# USB.net
KiCad netlist of a schematic drawn in Altium Designer
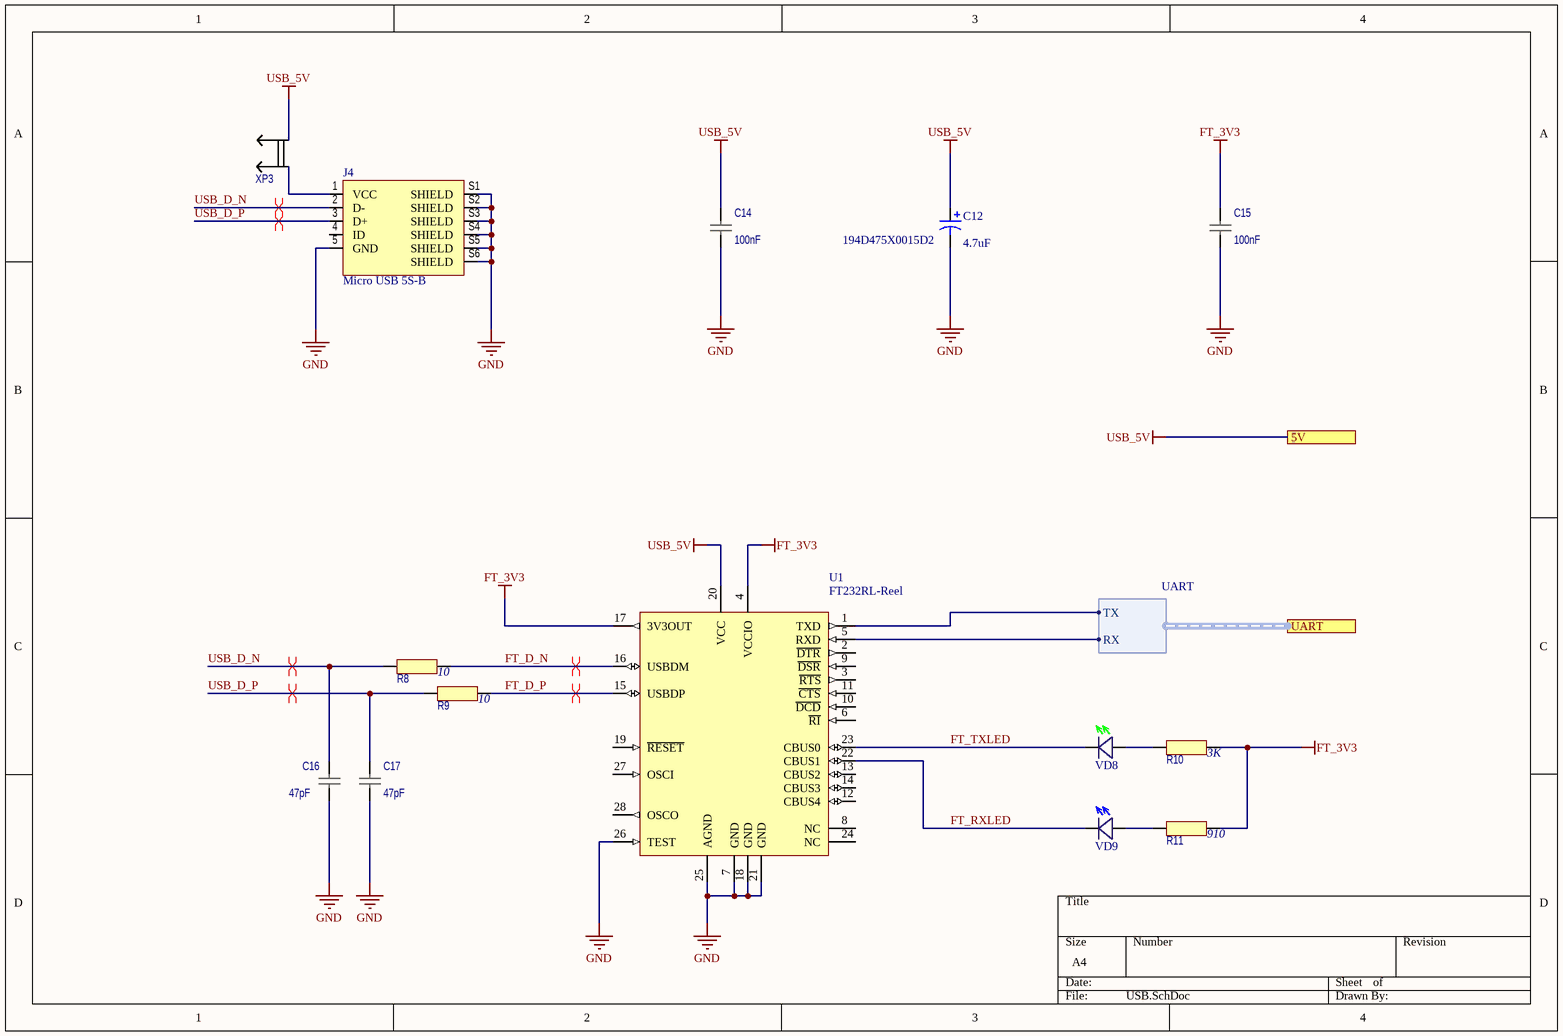
[diagram p0: USB.SchDoc]

(export (version "E")
  (design (tool "Eeschema 10.0.6"))
  (components
    (comp (ref "C12")
      (value "194D475X0015D2")
      (footprint "D")
      (fields (field (name "ALTIUM_VALUE") "4.7uF") (field (name "PUBLISHER") "Altium Limited"))
      (libsource (lib "Vishay Sprague Tantalum Chip Capacitor") (part "194D475X0015D2"))
    )
    (comp (ref "C14")
      (value "100nF")
      (footprint "C0805")
      (fields (field (name "TOLERANCE") "%") (field (name "VOLTAGE") "B") (field (name "Comment") "C0805"))
      (libsource (lib "my_AP_lib_sch") (part "C0805"))
    )
    (comp (ref "C15")
      (value "100nF")
      (footprint "C0805")
      (fields (field (name "TOLERANCE") "%") (field (name "VOLTAGE") "B") (field (name "Comment") "C0805"))
      (libsource (lib "my_AP_lib_sch") (part "C0805"))
    )
    (comp (ref "C16")
      (value "47pF")
      (footprint "C0805")
      (fields (field (name "TOLERANCE") "%") (field (name "VOLTAGE") "B") (field (name "Comment") "C0805"))
      (libsource (lib "my_AP_lib_sch") (part "C0805"))
    )
    (comp (ref "C17")
      (value "47pF")
      (footprint "C0805")
      (fields (field (name "TOLERANCE") "%") (field (name "VOLTAGE") "B") (field (name "Comment") "C0805"))
      (libsource (lib "my_AP_lib_sch") (part "C0805"))
    )
    (comp (ref "J4")
      (value "Micro USB 5S-B")
      (footprint "KLS1-233-0-0-1-T")
      (libsource (lib "my_AP_lib_sch") (part "KLS1-233-0-0-1-T"))
    )
    (comp (ref "R8")
      (value "10")
      (footprint "R0805")
      (fields (field (name "Comment") "R0805"))
      (libsource (lib "my_AP_lib_sch") (part "R0805"))
    )
    (comp (ref "R9")
      (value "10")
      (footprint "R0805")
      (fields (field (name "Comment") "R0805"))
      (libsource (lib "my_AP_lib_sch") (part "R0805"))
    )
    (comp (ref "R10")
      (value "3K")
      (footprint "R0805")
      (fields (field (name "Comment") "R0805"))
      (libsource (lib "my_AP_lib_sch") (part "R0805"))
    )
    (comp (ref "R11")
      (value "910")
      (footprint "R0805")
      (fields (field (name "Comment") "R0805"))
      (libsource (lib "my_AP_lib_sch") (part "R0805"))
    )
    (comp (ref "U1")
      (value "FT232RL-Reel")
      (footprint "SSOP-28_N")
      (description "USB UART Asynchronous Serial Data Transfer Chip, 28-pin SSOP, Tape and Reel")
      (fields (field (name "MANUFACTURER") "FTDI"))
      (libsource (lib "FTDI FT Series") (part "FT232RL-Reel"))
    )
    (comp (ref "VD8")
      (value "TO-1608BC-PG")
      (footprint "TO-1608BC-PG")
      (description "LED SMD 1608 705мКд, 120°, 525нМ (Pure Green)")
      (libsource (lib "my_AP_lib_sch") (part "TO-1608BC-PG"))
    )
    (comp (ref "VD9")
      (value "TO-1608BC-BF")
      (footprint "TO-1608BC-BF")
      (description "LED SMD 1608 247мКд, 120°, 468нМ (Blue)")
      (libsource (lib "my_AP_lib_sch") (part "TO-1608BC-BF"))
    )
    (comp (ref "XP3")
      (value "Замыкатель MJ-O-8KLS")
      (footprint "PLS-2")
      (fields (field (name "PARTNUMBER") "MJ-O-8KLS"))
      (libsource (lib "my_AP_lib_sch") (part "JP2"))
    )
  )
  (nets
    (net (code "2") (name "/FT_D_N") (class "Default")
      (node (ref "R8") (pin "1") (pinfunction "1_1") (pintype "passive"))
      (node (ref "U1") (pin "16") (pinfunction "USBDM_16") (pintype "bidirectional"))
    )
    (net (code "3") (name "/FT_D_P") (class "Default")
      (node (ref "R9") (pin "1") (pinfunction "1_1") (pintype "passive"))
      (node (ref "U1") (pin "15") (pinfunction "USBDP_15") (pintype "bidirectional"))
    )
    (net (code "4") (name "/FT_RXLED") (class "Default")
      (node (ref "U1") (pin "22") (pinfunction "CBUS1_22") (pintype "bidirectional"))
      (node (ref "VD9") (pin "-") (pinfunction "-_-") (pintype "passive"))
    )
    (net (code "5") (name "/FT_TXLED") (class "Default")
      (node (ref "U1") (pin "23") (pinfunction "CBUS0_23") (pintype "bidirectional"))
      (node (ref "VD8") (pin "-") (pinfunction "-_-") (pintype "passive"))
    )
    (net (code "6") (name "/RX") (class "Default")
      (node (ref "U1") (pin "5") (pinfunction "RXD_5") (pintype "input"))
    )
    (net (code "7") (name "/TX") (class "Default")
      (node (ref "U1") (pin "1") (pinfunction "TXD_1") (pintype "output"))
    )
    (net (code "8") (name "/USB_D_N") (class "Default")
      (node (ref "C16") (pin "2") (pinfunction "2_2") (pintype "passive"))
      (node (ref "J4") (pin "2") (pinfunction "D-_2") (pintype "passive"))
      (node (ref "R8") (pin "2") (pinfunction "2_2") (pintype "passive"))
    )
    (net (code "9") (name "/USB_D_P") (class "Default")
      (node (ref "C17") (pin "2") (pinfunction "2_2") (pintype "passive"))
      (node (ref "J4") (pin "3") (pinfunction "D+_3") (pintype "passive"))
      (node (ref "R9") (pin "2") (pinfunction "2_2") (pintype "passive"))
    )
    (net (code "11") (name "FT_3V3") (class "Default")
      (node (ref "C15") (pin "2") (pinfunction "2_2") (pintype "passive"))
      (node (ref "R10") (pin "1") (pinfunction "1_1") (pintype "passive"))
      (node (ref "R11") (pin "1") (pinfunction "1_1") (pintype "passive"))
      (node (ref "U1") (pin "17") (pinfunction "3V3OUT_17") (pintype "output"))
      (node (ref "U1") (pin "4") (pinfunction "VCCIO_4") (pintype "power_in"))
    )
    (net (code "12") (name "GND") (class "Default")
      (node (ref "C12") (pin "2") (pinfunction "2_2") (pintype "passive"))
      (node (ref "C14") (pin "1") (pinfunction "1_1") (pintype "passive"))
      (node (ref "C15") (pin "1") (pinfunction "1_1") (pintype "passive"))
      (node (ref "C16") (pin "1") (pinfunction "1_1") (pintype "passive"))
      (node (ref "C17") (pin "1") (pinfunction "1_1") (pintype "passive"))
      (node (ref "J4") (pin "5") (pinfunction "GND_5") (pintype "passive"))
      (node (ref "J4") (pin "S1") (pinfunction "SHIELD_S1") (pintype "passive"))
      (node (ref "J4") (pin "S2") (pinfunction "SHIELD_S2") (pintype "passive"))
      (node (ref "J4") (pin "S3") (pinfunction "SHIELD_S3") (pintype "passive"))
      (node (ref "J4") (pin "S4") (pinfunction "SHIELD_S4") (pintype "passive"))
      (node (ref "J4") (pin "S5") (pinfunction "SHIELD_S5") (pintype "passive"))
      (node (ref "J4") (pin "S6") (pinfunction "SHIELD_S6") (pintype "passive"))
      (node (ref "U1") (pin "18") (pinfunction "GND_18") (pintype "power_in"))
      (node (ref "U1") (pin "21") (pinfunction "GND_21") (pintype "power_in"))
      (node (ref "U1") (pin "25") (pinfunction "AGND_25") (pintype "power_in"))
      (node (ref "U1") (pin "26") (pinfunction "TEST_26") (pintype "input"))
      (node (ref "U1") (pin "7") (pinfunction "GND_7") (pintype "power_in"))
    )
    (net (code "13") (name "Net-(J4-VCC)") (class "Default")
      (node (ref "J4") (pin "1") (pinfunction "VCC_1") (pintype "passive"))
      (node (ref "XP3") (pin "1") (pinfunction "1_1") (pintype "passive"))
    )
    (net (code "14") (name "Net-(R10-Pad2)") (class "Default")
      (node (ref "R10") (pin "2") (pinfunction "2_2") (pintype "passive"))
      (node (ref "VD8") (pin "+") (pinfunction "+_+") (pintype "passive"))
    )
    (net (code "15") (name "Net-(R11-Pad2)") (class "Default")
      (node (ref "R11") (pin "2") (pinfunction "2_2") (pintype "passive"))
      (node (ref "VD9") (pin "+") (pinfunction "+_+") (pintype "passive"))
    )
    (net (code "16") (name "USB_5V") (class "Default")
      (node (ref "C12") (pin "1") (pinfunction "1_1") (pintype "passive"))
      (node (ref "C14") (pin "2") (pinfunction "2_2") (pintype "passive"))
      (node (ref "U1") (pin "20") (pinfunction "VCC_20") (pintype "power_in"))
      (node (ref "XP3") (pin "2") (pinfunction "2_2") (pintype "passive"))
    )
    (net (code "17") (name "unconnected-(J4-ID-Pad4)") (class "Default")
      (node (ref "J4") (pin "4") (pinfunction "ID_4") (pintype "passive"))
    )
    (net (code "18") (name "unconnected-(U1-CBUS2-Pad13)") (class "Default")
      (node (ref "U1") (pin "13") (pinfunction "CBUS2_13") (pintype "bidirectional"))
    )
    (net (code "19") (name "unconnected-(U1-CBUS3-Pad14)") (class "Default")
      (node (ref "U1") (pin "14") (pinfunction "CBUS3_14") (pintype "bidirectional"))
    )
    (net (code "20") (name "unconnected-(U1-CBUS4-Pad12)") (class "Default")
      (node (ref "U1") (pin "12") (pinfunction "CBUS4_12") (pintype "bidirectional"))
    )
    (net (code "21") (name "unconnected-(U1-NC-Pad8)") (class "Default")
      (node (ref "U1") (pin "8") (pinfunction "NC_8") (pintype "passive"))
    )
    (net (code "22") (name "unconnected-(U1-NC-Pad24)") (class "Default")
      (node (ref "U1") (pin "24") (pinfunction "NC_24") (pintype "passive"))
    )
    (net (code "23") (name "unconnected-(U1-OSCI-Pad27)") (class "Default")
      (node (ref "U1") (pin "27") (pinfunction "OSCI_27") (pintype "input"))
    )
    (net (code "24") (name "unconnected-(U1-OSCO-Pad28)") (class "Default")
      (node (ref "U1") (pin "28") (pinfunction "OSCO_28") (pintype "output"))
    )
    (net (code "25") (name "unconnected-(U1-~{CTS}-Pad11)") (class "Default")
      (node (ref "U1") (pin "11") (pinfunction "~{CTS}_11") (pintype "input"))
    )
    (net (code "26") (name "unconnected-(U1-~{DCD}-Pad10)") (class "Default")
      (node (ref "U1") (pin "10") (pinfunction "~{DCD}_10") (pintype "input"))
    )
    (net (code "27") (name "unconnected-(U1-~{DSR}-Pad9)") (class "Default")
      (node (ref "U1") (pin "9") (pinfunction "~{DSR}_9") (pintype "input"))
    )
    (net (code "28") (name "unconnected-(U1-~{DTR}-Pad2)") (class "Default")
      (node (ref "U1") (pin "2") (pinfunction "~{DTR}_2") (pintype "output"))
    )
    (net (code "29") (name "unconnected-(U1-~{RESET}-Pad19)") (class "Default")
      (node (ref "U1") (pin "19") (pinfunction "~{RESET}_19") (pintype "input"))
    )
    (net (code "30") (name "unconnected-(U1-~{RI}-Pad6)") (class "Default")
      (node (ref "U1") (pin "6") (pinfunction "~{RI}_6") (pintype "input"))
    )
    (net (code "31") (name "unconnected-(U1-~{RTS}-Pad3)") (class "Default")
      (node (ref "U1") (pin "3") (pinfunction "~{RTS}_3") (pintype "output"))
    )
  )
)
